# acdimmer-revB.net
KiCad netlist of a schematic drawn in EAGLE
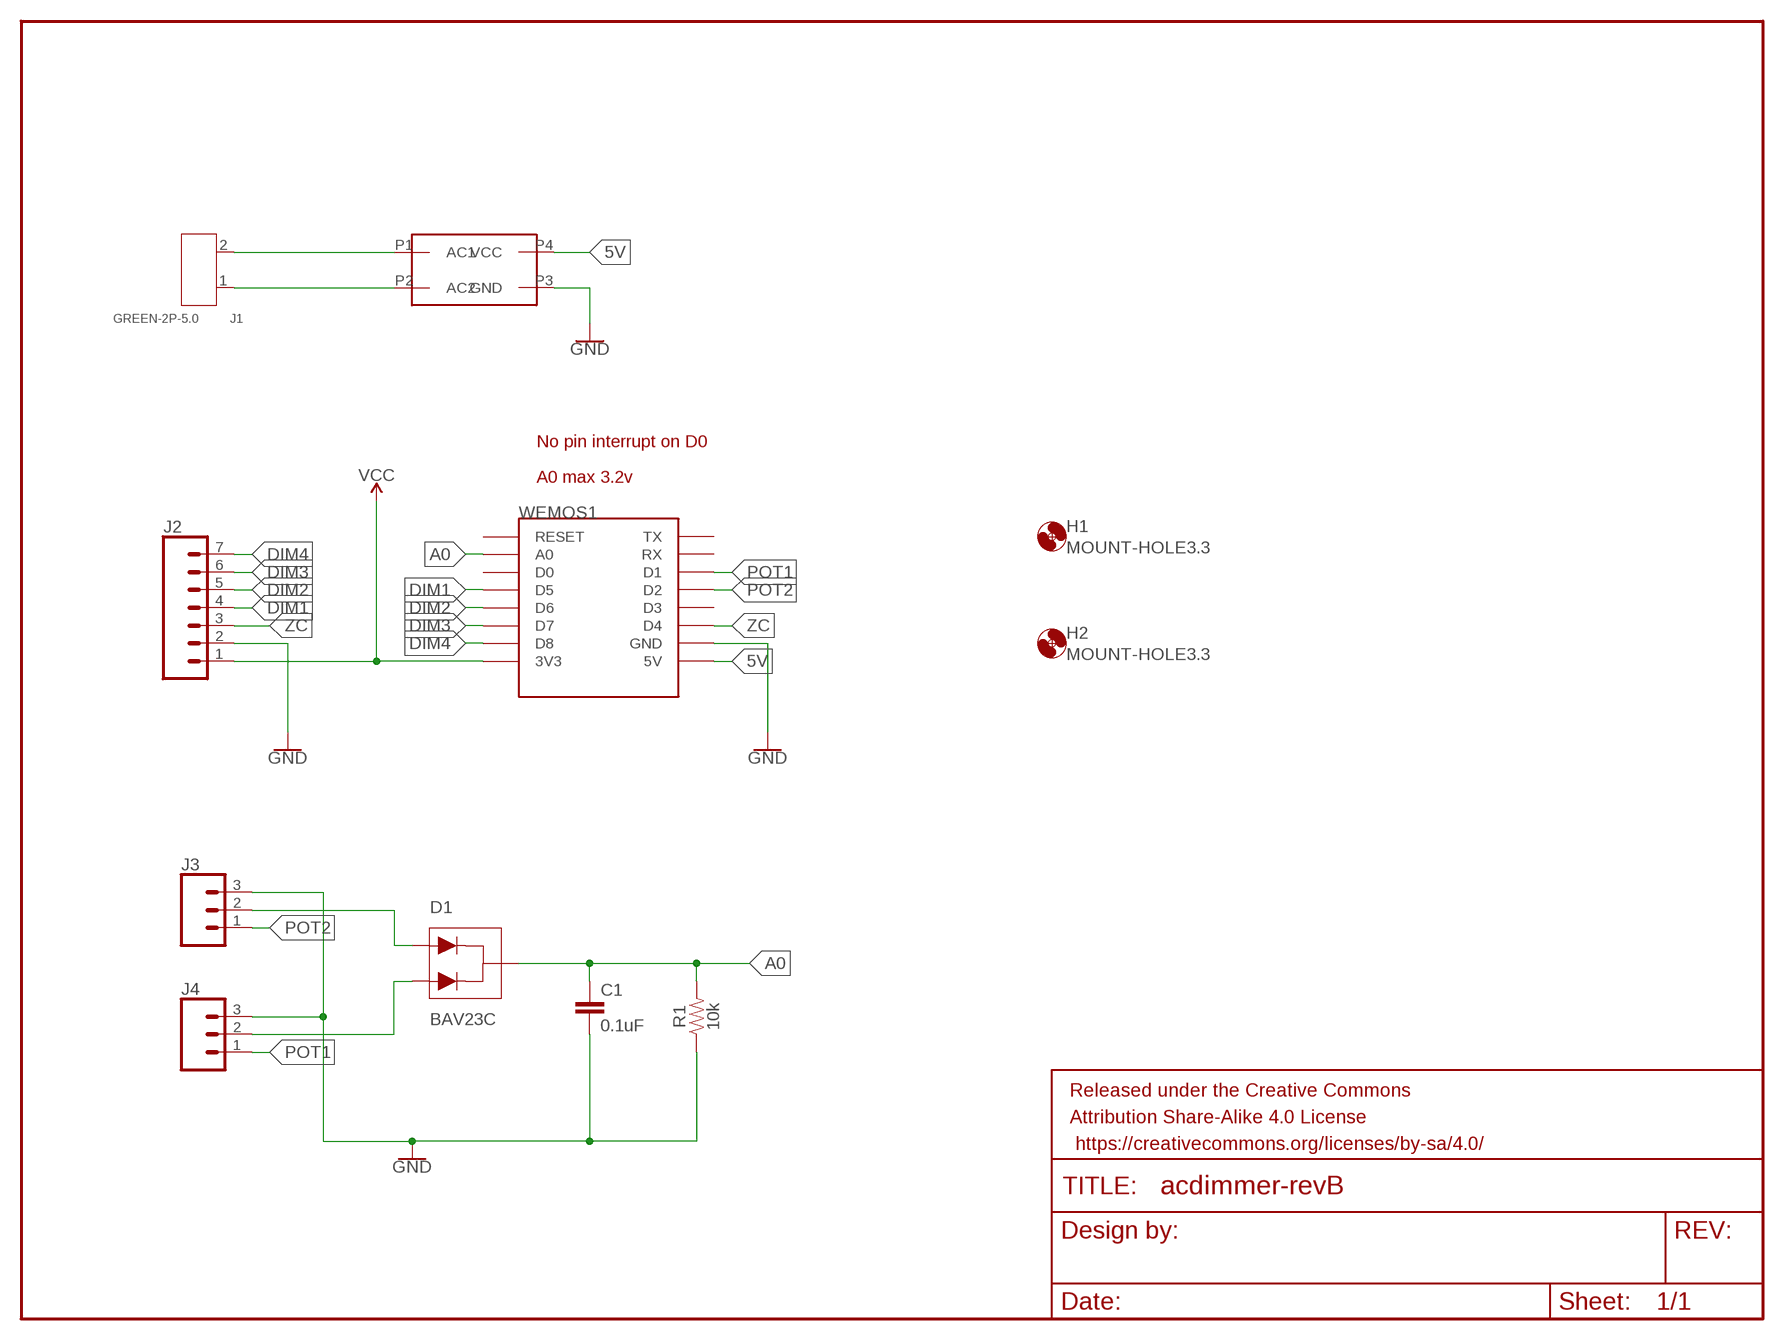
[diagram p0: schematic, sheet 1]

(export (version "E")
  (design (tool "Eeschema 10.0.6"))
  (components
    (comp (ref "C1")
      (value "0.1uF")
      (footprint "eagle-import:0603")
      (libsource (lib "eagle-import") (part "0.1UF-0603-25V-5%"))
    )
    (comp (ref "D1")
      (value "BAV23C")
      (footprint "eagle-import:SOT23-3")
      (libsource (lib "eagle-import") (part "BAV23C"))
    )
    (comp (ref "FRAME1")
      (value "FRAME-LETTERNO_PACKAGE")
      (footprint "eagle-import:DUMMY")
      (fields (field (name "DESIGNER") "Nobody"))
      (libsource (lib "eagle-import") (part "FRAME-LETTERNO_PACKAGE"))
    )
    (comp (ref "H1")
      (value "MOUNT-HOLE3.3")
      (footprint "eagle-import:3,3")
      (libsource (lib "eagle-import") (part "MOUNT-HOLE3.3"))
    )
    (comp (ref "H2")
      (value "MOUNT-HOLE3.3")
      (footprint "eagle-import:3,3")
      (libsource (lib "eagle-import") (part "MOUNT-HOLE3.3"))
    )
    (comp (ref "J1")
      (value "GREEN-2P-5.0")
      (footprint "eagle-import:H2-5.0-10.5X8.0MM")
      (libsource (lib "eagle-import") (part "SCREW-TERMINAL-GREEN(2P-5.0)"))
    )
    (comp (ref "J2")
      (value "CONN_07NO_SILK")
      (footprint "eagle-import:1X07_NO_SILK")
      (libsource (lib "eagle-import") (part "CONN_07NO_SILK"))
    )
    (comp (ref "J3")
      (value "CONN_03SCREW")
      (footprint "eagle-import:SCREWTERMINAL-3.5MM-3")
      (libsource (lib "eagle-import") (part "CONN_03SCREW"))
    )
    (comp (ref "J4")
      (value "CONN_03SCREW")
      (footprint "eagle-import:SCREWTERMINAL-3.5MM-3")
      (libsource (lib "eagle-import") (part "CONN_03SCREW"))
    )
    (comp (ref "R1")
      (value "10k")
      (footprint "eagle-import:0603")
      (libsource (lib "eagle-import") (part "10KOHM-0603-1/10W-1%"))
    )
    (comp (ref "U$1")
      (value "ACDC5V")
      (footprint "eagle-import:ACDC5V")
      (libsource (lib "eagle-import") (part "ACDC5V"))
    )
    (comp (ref "WEMOS1")
      (value "WEMOS-D1-MINI")
      (footprint "eagle-import:WEMOS-D1-MINI")
      (libsource (lib "eagle-import") (part "WEMOS-D1-MINI"))
    )
  )
  (nets
    (net (code "1") (name "5V") (class "Default")
      (node (ref "U$1") (pin "P4") (pinfunction "VCC_P4") (pintype "bidirectional"))
      (node (ref "WEMOS1") (pin "5V") (pinfunction "5V_5V") (pintype "bidirectional"))
    )
    (net (code "2") (name "A0") (class "Default")
      (node (ref "C1") (pin "1") (pinfunction "1_1") (pintype "passive"))
      (node (ref "D1") (pin "3") (pinfunction "C_3") (pintype "passive"))
      (node (ref "R1") (pin "2") (pinfunction "2_2") (pintype "passive"))
      (node (ref "WEMOS1") (pin "A0") (pinfunction "A0_A0") (pintype "bidirectional"))
    )
    (net (code "3") (name "DIM1") (class "Default")
      (node (ref "J2") (pin "4") (pinfunction "4_4") (pintype "passive"))
      (node (ref "WEMOS1") (pin "D5") (pinfunction "D5_D5") (pintype "bidirectional"))
    )
    (net (code "4") (name "DIM2") (class "Default")
      (node (ref "J2") (pin "5") (pinfunction "5_5") (pintype "passive"))
      (node (ref "WEMOS1") (pin "D6") (pinfunction "D6_D6") (pintype "bidirectional"))
    )
    (net (code "5") (name "DIM3") (class "Default")
      (node (ref "J2") (pin "6") (pinfunction "6_6") (pintype "passive"))
      (node (ref "WEMOS1") (pin "D7") (pinfunction "D7_D7") (pintype "bidirectional"))
    )
    (net (code "6") (name "DIM4") (class "Default")
      (node (ref "J2") (pin "7") (pinfunction "7_7") (pintype "passive"))
      (node (ref "WEMOS1") (pin "D8") (pinfunction "D8_D8") (pintype "bidirectional"))
    )
    (net (code "7") (name "GND") (class "Default")
      (node (ref "C1") (pin "2") (pinfunction "2_2") (pintype "passive"))
      (node (ref "J2") (pin "2") (pinfunction "2_2") (pintype "passive"))
      (node (ref "J3") (pin "3") (pinfunction "3_3") (pintype "passive"))
      (node (ref "J4") (pin "3") (pinfunction "3_3") (pintype "passive"))
      (node (ref "R1") (pin "1") (pinfunction "1_1") (pintype "passive"))
      (node (ref "U$1") (pin "P3") (pinfunction "GND_P3") (pintype "bidirectional"))
      (node (ref "WEMOS1") (pin "GND") (pinfunction "GND_GND") (pintype "bidirectional"))
    )
    (net (code "8") (name "Net-(D1-A1)") (class "Default")
      (node (ref "D1") (pin "1") (pinfunction "A1_1") (pintype "passive"))
      (node (ref "J3") (pin "2") (pinfunction "2_2") (pintype "passive"))
    )
    (net (code "9") (name "Net-(D1-A2)") (class "Default")
      (node (ref "D1") (pin "2") (pinfunction "A2_2") (pintype "passive"))
      (node (ref "J4") (pin "2") (pinfunction "2_2") (pintype "passive"))
    )
    (net (code "10") (name "Net-(U$1-AC1)") (class "Default")
      (node (ref "J1") (pin "2") (pinfunction "2_2") (pintype "bidirectional"))
      (node (ref "U$1") (pin "P1") (pinfunction "AC1_P1") (pintype "bidirectional"))
    )
    (net (code "11") (name "Net-(U$1-AC2)") (class "Default")
      (node (ref "J1") (pin "1") (pinfunction "1_1") (pintype "bidirectional"))
      (node (ref "U$1") (pin "P2") (pinfunction "AC2_P2") (pintype "bidirectional"))
    )
    (net (code "12") (name "POT1") (class "Default")
      (node (ref "J4") (pin "1") (pinfunction "1_1") (pintype "passive"))
      (node (ref "WEMOS1") (pin "D1") (pinfunction "D1_D1") (pintype "bidirectional"))
    )
    (net (code "13") (name "POT2") (class "Default")
      (node (ref "J3") (pin "1") (pinfunction "1_1") (pintype "passive"))
      (node (ref "WEMOS1") (pin "D2") (pinfunction "D2_D2") (pintype "bidirectional"))
    )
    (net (code "14") (name "VCC") (class "Default")
      (node (ref "J2") (pin "1") (pinfunction "1_1") (pintype "passive"))
      (node (ref "WEMOS1") (pin "3V3") (pinfunction "3V3_3V3") (pintype "bidirectional"))
    )
    (net (code "15") (name "ZC") (class "Default")
      (node (ref "J2") (pin "3") (pinfunction "3_3") (pintype "passive"))
      (node (ref "WEMOS1") (pin "D4") (pinfunction "D4_D4") (pintype "bidirectional"))
    )
    (net (code "16") (name "unconnected-(WEMOS1-PadD0)") (class "Default")
      (node (ref "WEMOS1") (pin "D0") (pinfunction "D0_D0") (pintype "bidirectional"))
    )
    (net (code "17") (name "unconnected-(WEMOS1-PadD3)") (class "Default")
      (node (ref "WEMOS1") (pin "D3") (pinfunction "D3_D3") (pintype "bidirectional"))
    )
    (net (code "18") (name "unconnected-(WEMOS1-PadRESET)") (class "Default")
      (node (ref "WEMOS1") (pin "RESET") (pinfunction "RESET_RESET") (pintype "bidirectional"))
    )
    (net (code "19") (name "unconnected-(WEMOS1-PadRX)") (class "Default")
      (node (ref "WEMOS1") (pin "RX") (pinfunction "RX_RX") (pintype "bidirectional"))
    )
    (net (code "20") (name "unconnected-(WEMOS1-PadTX)") (class "Default")
      (node (ref "WEMOS1") (pin "TX") (pinfunction "TX_TX") (pintype "bidirectional"))
    )
  )
)
